# PCU_R3.net
KiCad netlist of a schematic drawn in EAGLE
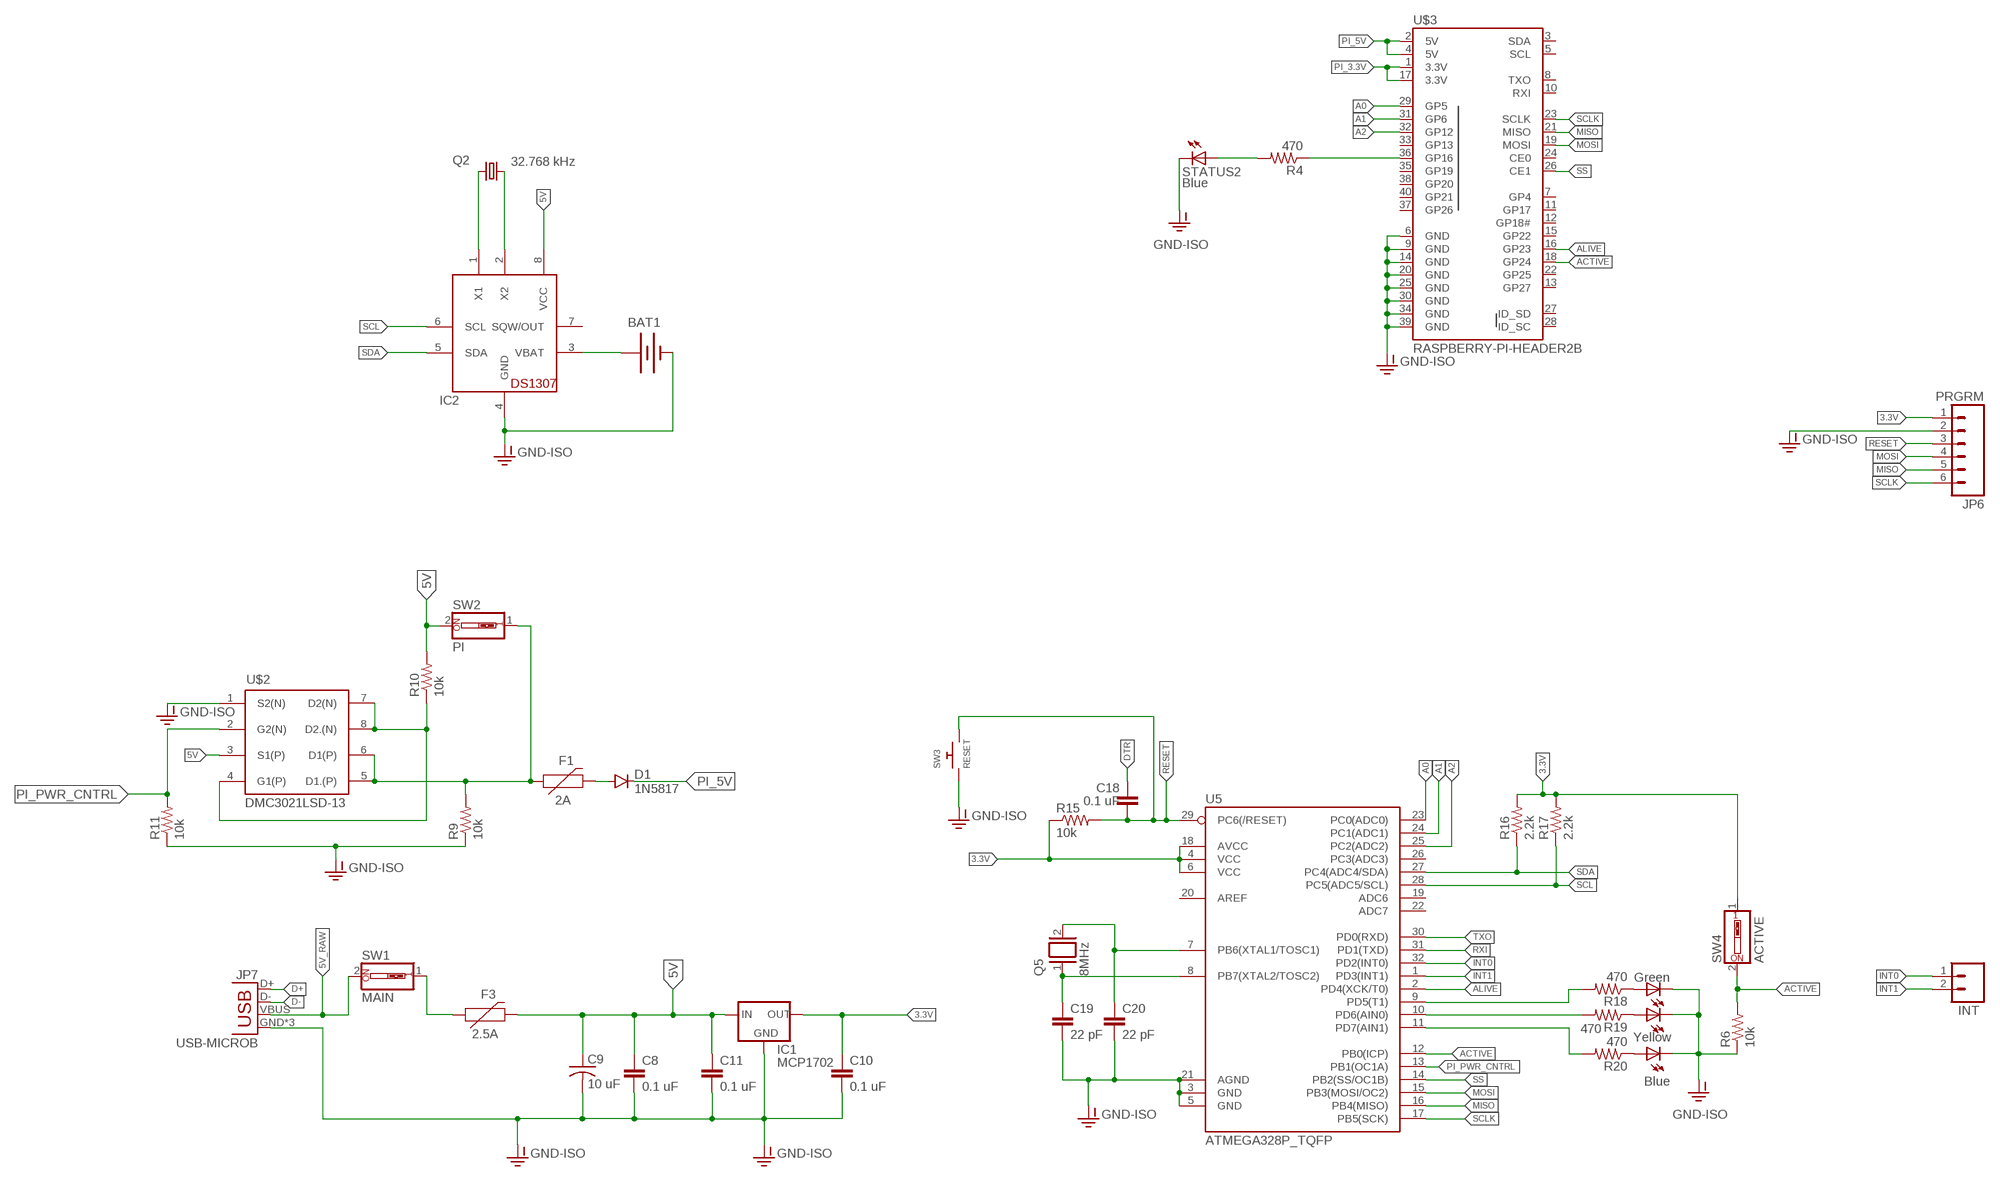
[diagram p0: schematic, sheet 1]

(export (version "E")
  (design (tool "Eeschema 10.0.6"))
  (components
    (comp (ref "BAT1")
      (value "BATTERY12MM")
      (footprint "eagle-import:BATTCON_12MM")
      (libsource (lib "eagle-import") (part "BATTERY12MM"))
    )
    (comp (ref "C8")
      (value "0.1 uF")
      (footprint "eagle-import:1206")
      (libsource (lib "eagle-import") (part "1.0UF-1206-50V-10%"))
    )
    (comp (ref "C9")
      (value "10 uF")
      (footprint "eagle-import:C1206")
      (libsource (lib "eagle-import") (part "C-USC1206"))
    )
    (comp (ref "C10")
      (value "0.1 uF")
      (footprint "eagle-import:1206")
      (libsource (lib "eagle-import") (part "1.0UF-1206-50V-10%"))
    )
    (comp (ref "C11")
      (value "0.1 uF")
      (footprint "eagle-import:1206")
      (libsource (lib "eagle-import") (part "1.0UF-1206-50V-10%"))
    )
    (comp (ref "C18")
      (value "0.1 uF")
      (footprint "eagle-import:1206")
      (libsource (lib "eagle-import") (part "1.0UF-1206-50V-10%"))
    )
    (comp (ref "C19")
      (value "22 pF")
      (footprint "eagle-import:1206")
      (libsource (lib "eagle-import") (part "1.0UF-1206-50V-10%"))
    )
    (comp (ref "C20")
      (value "22 pF")
      (footprint "eagle-import:1206")
      (libsource (lib "eagle-import") (part "1.0UF-1206-50V-10%"))
    )
    (comp (ref "D1")
      (value "1N5817")
      (footprint "eagle-import:DIODE-1N4001")
      (libsource (lib "eagle-import") (part "DIODEPTH"))
    )
    (comp (ref "F1")
      (value "2A")
      (footprint "eagle-import:1206")
      (libsource (lib "eagle-import") (part "PPTC_HALF-AMP"))
    )
    (comp (ref "F3")
      (value "2.5A")
      (footprint "eagle-import:1206")
      (libsource (lib "eagle-import") (part "PPTC_HALF-AMP"))
    )
    (comp (ref "IC1")
      (value "MCP1702")
      (footprint "eagle-import:TO92")
      (libsource (lib "eagle-import") (part "MCP1700TRI"))
    )
    (comp (ref "IC2")
      (value "DS1307")
      (footprint "eagle-import:DIL08")
      (libsource (lib "eagle-import") (part "DS1307"))
    )
    (comp (ref "INT")
      (value "M02PTH")
      (footprint "eagle-import:1X02")
      (libsource (lib "eagle-import") (part "M02PTH"))
    )
    (comp (ref "JP6")
      (value "PRGRM")
      (footprint "eagle-import:1X06")
      (libsource (lib "eagle-import") (part "M06SILK_FEMALE_PTH"))
    )
    (comp (ref "JP7")
      (value "USB-MICROB")
      (footprint "eagle-import:USB-MICROB")
      (libsource (lib "eagle-import") (part "USB-MICROB"))
    )
    (comp (ref "LED6")
      (value "Green")
      (footprint "eagle-import:CHIPLED_1206")
      (libsource (lib "eagle-import") (part "LEDCHIPLED_1206"))
    )
    (comp (ref "LED7")
      (value "Yellow")
      (footprint "eagle-import:CHIPLED_1206")
      (libsource (lib "eagle-import") (part "LEDCHIPLED_1206"))
    )
    (comp (ref "LED8")
      (value "Blue")
      (footprint "eagle-import:CHIPLED_1206")
      (libsource (lib "eagle-import") (part "LEDCHIPLED_1206"))
    )
    (comp (ref "Q2")
      (value "32.768 kHz")
      (footprint "eagle-import:TC38H")
      (libsource (lib "eagle-import") (part "CRYSTALTC38H"))
    )
    (comp (ref "Q5")
      (value "8MHz")
      (footprint "eagle-import:QS")
      (libsource (lib "eagle-import") (part "XTAL/S"))
    )
    (comp (ref "R4")
      (value "470")
      (footprint "eagle-import:1206")
      (libsource (lib "eagle-import") (part "RESISTOR1206"))
    )
    (comp (ref "R6")
      (value "10k")
      (footprint "eagle-import:1206")
      (libsource (lib "eagle-import") (part "RESISTOR1206"))
    )
    (comp (ref "R9")
      (value "10k")
      (footprint "eagle-import:R1206")
      (libsource (lib "eagle-import") (part "R-US_R1206"))
    )
    (comp (ref "R10")
      (value "10k")
      (footprint "eagle-import:R1206")
      (libsource (lib "eagle-import") (part "R-US_R1206"))
    )
    (comp (ref "R11")
      (value "10k")
      (footprint "eagle-import:R1206")
      (libsource (lib "eagle-import") (part "R-US_R1206"))
    )
    (comp (ref "R15")
      (value "10k")
      (footprint "eagle-import:1206")
      (libsource (lib "eagle-import") (part "RESISTOR1206"))
    )
    (comp (ref "R16")
      (value "2.2k")
      (footprint "eagle-import:1206")
      (libsource (lib "eagle-import") (part "RESISTOR1206"))
    )
    (comp (ref "R17")
      (value "2.2k")
      (footprint "eagle-import:1206")
      (libsource (lib "eagle-import") (part "RESISTOR1206"))
    )
    (comp (ref "R18")
      (value "470")
      (footprint "eagle-import:1206")
      (libsource (lib "eagle-import") (part "RESISTOR1206"))
    )
    (comp (ref "R19")
      (value "470")
      (footprint "eagle-import:1206")
      (libsource (lib "eagle-import") (part "RESISTOR1206"))
    )
    (comp (ref "R20")
      (value "470")
      (footprint "eagle-import:1206")
      (libsource (lib "eagle-import") (part "RESISTOR1206"))
    )
    (comp (ref "STATUS2")
      (value "Blue")
      (footprint "eagle-import:CHIPLED_1206")
      (libsource (lib "eagle-import") (part "LEDCHIPLED_1206"))
    )
    (comp (ref "SW1")
      (value "MAIN")
      (footprint "eagle-import:EDG-01")
      (libsource (lib "eagle-import") (part "SW_DIP-1"))
    )
    (comp (ref "SW2")
      (value "PI")
      (footprint "eagle-import:EDG-01")
      (libsource (lib "eagle-import") (part "SW_DIP-1"))
    )
    (comp (ref "SW3")
      (value "RESET")
      (footprint "eagle-import:PUSHBUTTON_SMD_SJ")
      (libsource (lib "eagle-import") (part "SWITCH_PUSHBUTTONSOFTTOUCHSMD_SJ"))
    )
    (comp (ref "SW4")
      (value "ACTIVE")
      (footprint "eagle-import:EDG-01")
      (libsource (lib "eagle-import") (part "SW_DIP-1"))
    )
    (comp (ref "U$2")
      (value "DMC3021LSD-13")
      (footprint "eagle-import:SOIC-8")
      (libsource (lib "eagle-import") (part "DMC3021LSD-13"))
    )
    (comp (ref "U$3")
      (value "RASPBERRY-PI-HEADER2B")
      (footprint "eagle-import:2X20-NOSILK")
      (libsource (lib "eagle-import") (part "RASPBERRY-PI-HEADER2B"))
    )
    (comp (ref "U5")
      (value "ATMEGA328P_TQFP")
      (footprint "eagle-import:TQFP32-08")
      (libsource (lib "eagle-import") (part "ATMEGA328P_TQFP"))
    )
  )
  (nets
    (net (code "1") (name "3.3V") (class "Default")
      (node (ref "C10") (pin "1") (pinfunction "1_1") (pintype "passive"))
      (node (ref "IC1") (pin "3") (pinfunction "OUT_3") (pintype "passive"))
      (node (ref "JP6") (pin "1") (pinfunction "1_1") (pintype "passive"))
      (node (ref "R15") (pin "1") (pinfunction "1_1") (pintype "passive"))
      (node (ref "R16") (pin "2") (pinfunction "2_2") (pintype "passive"))
      (node (ref "R17") (pin "2") (pinfunction "2_2") (pintype "passive"))
      (node (ref "SW4") (pin "1") (pinfunction "1_1") (pintype "passive"))
      (node (ref "U5") (pin "18") (pinfunction "AVCC_18") (pintype "bidirectional"))
      (node (ref "U5") (pin "4") (pinfunction "VCC_4") (pintype "bidirectional"))
      (node (ref "U5") (pin "6") (pinfunction "VCC_6") (pintype "bidirectional"))
    )
    (net (code "2") (name "5V") (class "Default")
      (node (ref "C11") (pin "1") (pinfunction "1_1") (pintype "passive"))
      (node (ref "C8") (pin "1") (pinfunction "1_1") (pintype "passive"))
      (node (ref "C9") (pin "1") (pinfunction "1_1") (pintype "passive"))
      (node (ref "F3") (pin "2") (pinfunction "2_2") (pintype "bidirectional"))
      (node (ref "IC1") (pin "2") (pinfunction "IN_2") (pintype "input"))
      (node (ref "IC2") (pin "8") (pinfunction "VCC_8") (pintype "power_in"))
      (node (ref "R10") (pin "2") (pinfunction "2_2") (pintype "passive"))
      (node (ref "SW2") (pin "2") (pinfunction "2_2") (pintype "passive"))
      (node (ref "U$2") (pin "3") (pinfunction "S1(P)_3") (pintype "bidirectional"))
    )
    (net (code "3") (name "5V_RAW") (class "Default")
      (node (ref "JP7") (pin "VBUS") (pinfunction "VBUS_VBUS") (pintype "bidirectional"))
      (node (ref "SW1") (pin "2") (pinfunction "2_2") (pintype "passive"))
    )
    (net (code "4") (name "A0") (class "Default")
      (node (ref "U$3") (pin "29") (pinfunction "GP5_29") (pintype "bidirectional"))
      (node (ref "U5") (pin "23") (pinfunction "PC0(ADC0)_23") (pintype "bidirectional"))
    )
    (net (code "5") (name "A1") (class "Default")
      (node (ref "U$3") (pin "31") (pinfunction "GP6_31") (pintype "bidirectional"))
      (node (ref "U5") (pin "24") (pinfunction "PC1(ADC1)_24") (pintype "bidirectional"))
    )
    (net (code "6") (name "A2") (class "Default")
      (node (ref "U$3") (pin "32") (pinfunction "GP12_32") (pintype "bidirectional"))
      (node (ref "U5") (pin "25") (pinfunction "PC2(ADC2)_25") (pintype "bidirectional"))
    )
    (net (code "7") (name "ACTIVE") (class "Default")
      (node (ref "R6") (pin "2") (pinfunction "2_2") (pintype "passive"))
      (node (ref "SW4") (pin "2") (pinfunction "2_2") (pintype "passive"))
      (node (ref "U$3") (pin "18") (pinfunction "GP24_18") (pintype "bidirectional"))
      (node (ref "U5") (pin "12") (pinfunction "PB0(ICP)_12") (pintype "bidirectional"))
    )
    (net (code "8") (name "ALIVE") (class "Default")
      (node (ref "U$3") (pin "16") (pinfunction "GP23_16") (pintype "bidirectional"))
      (node (ref "U5") (pin "2") (pinfunction "PD4(XCK/T0)_2") (pintype "bidirectional"))
    )
    (net (code "9") (name "D+") (class "Default")
      (node (ref "JP7") (pin "D+") (pinfunction "D+_D+") (pintype "bidirectional"))
    )
    (net (code "10") (name "D-") (class "Default")
      (node (ref "JP7") (pin "D-") (pinfunction "D-_D-") (pintype "bidirectional"))
    )
    (net (code "11") (name "DTR") (class "Default")
      (node (ref "C18") (pin "1") (pinfunction "1_1") (pintype "passive"))
    )
    (net (code "12") (name "GND-ISO") (class "Default")
      (node (ref "BAT1") (pin "GND") (pinfunction "-_GND") (pintype "power_in"))
      (node (ref "C10") (pin "2") (pinfunction "2_2") (pintype "passive"))
      (node (ref "C11") (pin "2") (pinfunction "2_2") (pintype "passive"))
      (node (ref "C19") (pin "2") (pinfunction "2_2") (pintype "passive"))
      (node (ref "C20") (pin "2") (pinfunction "2_2") (pintype "passive"))
      (node (ref "C8") (pin "2") (pinfunction "2_2") (pintype "passive"))
      (node (ref "C9") (pin "2") (pinfunction "2_2") (pintype "passive"))
      (node (ref "IC1") (pin "1") (pinfunction "GND_1") (pintype "input"))
      (node (ref "IC2") (pin "4") (pinfunction "GND_4") (pintype "power_in"))
      (node (ref "JP6") (pin "2") (pinfunction "2_2") (pintype "passive"))
      (node (ref "JP7") (pin "GND") (pinfunction "GND_GND") (pintype "bidirectional"))
      (node (ref "JP7") (pin "MT1") (pinfunction "GND_MT1") (pintype "bidirectional"))
      (node (ref "JP7") (pin "MT2") (pinfunction "GND_MT2") (pintype "bidirectional"))
      (node (ref "LED6") (pin "C") (pinfunction "C_C") (pintype "passive"))
      (node (ref "LED7") (pin "C") (pinfunction "C_C") (pintype "passive"))
      (node (ref "LED8") (pin "C") (pinfunction "C_C") (pintype "passive"))
      (node (ref "R11") (pin "1") (pinfunction "1_1") (pintype "passive"))
      (node (ref "R6") (pin "1") (pinfunction "1_1") (pintype "passive"))
      (node (ref "R9") (pin "1") (pinfunction "1_1") (pintype "passive"))
      (node (ref "STATUS2") (pin "C") (pinfunction "C_C") (pintype "passive"))
      (node (ref "SW3") (pin "P$1") (pinfunction "P$1_P$1") (pintype "passive"))
      (node (ref "U$2") (pin "1") (pinfunction "S2(N)_1") (pintype "bidirectional"))
      (node (ref "U$3") (pin "14") (pinfunction "GND_14") (pintype "power_in"))
      (node (ref "U$3") (pin "20") (pinfunction "GND_20") (pintype "power_in"))
      (node (ref "U$3") (pin "25") (pinfunction "GND_25") (pintype "power_in"))
      (node (ref "U$3") (pin "30") (pinfunction "GND_30") (pintype "power_in"))
      (node (ref "U$3") (pin "34") (pinfunction "GND_34") (pintype "power_in"))
      (node (ref "U$3") (pin "39") (pinfunction "GND_39") (pintype "power_in"))
      (node (ref "U$3") (pin "6") (pinfunction "GND_6") (pintype "power_in"))
      (node (ref "U$3") (pin "9") (pinfunction "GND_9") (pintype "power_in"))
      (node (ref "U5") (pin "21") (pinfunction "AGND_21") (pintype "bidirectional"))
      (node (ref "U5") (pin "3") (pinfunction "GND_3") (pintype "bidirectional"))
      (node (ref "U5") (pin "5") (pinfunction "GND_5") (pintype "bidirectional"))
    )
    (net (code "13") (name "INT0") (class "Default")
      (node (ref "INT") (pin "1") (pinfunction "1_1") (pintype "passive"))
      (node (ref "U5") (pin "32") (pinfunction "PD2(INT0)_32") (pintype "bidirectional"))
    )
    (net (code "14") (name "INT1") (class "Default")
      (node (ref "INT") (pin "2") (pinfunction "2_2") (pintype "passive"))
      (node (ref "U5") (pin "1") (pinfunction "PD3(INT1)_1") (pintype "bidirectional"))
    )
    (net (code "15") (name "MISO") (class "Default")
      (node (ref "JP6") (pin "5") (pinfunction "5_5") (pintype "passive"))
      (node (ref "U$3") (pin "21") (pinfunction "MISO_21") (pintype "input"))
      (node (ref "U5") (pin "16") (pinfunction "PB4(MISO)_16") (pintype "bidirectional"))
    )
    (net (code "16") (name "MOSI") (class "Default")
      (node (ref "JP6") (pin "4") (pinfunction "4_4") (pintype "passive"))
      (node (ref "U$3") (pin "19") (pinfunction "MOSI_19") (pintype "output"))
      (node (ref "U5") (pin "15") (pinfunction "PB3(MOSI/OC2)_15") (pintype "bidirectional"))
    )
    (net (code "17") (name "Net-(BAT1-+)") (class "Default")
      (node (ref "BAT1") (pin "PWR@1") (pinfunction "+_PWR@1") (pintype "power_in"))
      (node (ref "IC2") (pin "3") (pinfunction "VBAT_3") (pintype "power_in"))
    )
    (net (code "18") (name "Net-(D1-PadA)") (class "Default")
      (node (ref "D1") (pin "A") (pinfunction "A_A") (pintype "passive"))
      (node (ref "F1") (pin "2") (pinfunction "2_2") (pintype "bidirectional"))
    )
    (net (code "19") (name "Net-(F3-Pad1)") (class "Default")
      (node (ref "F3") (pin "1") (pinfunction "1_1") (pintype "bidirectional"))
      (node (ref "SW1") (pin "1") (pinfunction "1_1") (pintype "passive"))
    )
    (net (code "20") (name "Net-(IC2-X1)") (class "Default")
      (node (ref "IC2") (pin "1") (pinfunction "X1_1") (pintype "passive"))
      (node (ref "Q2") (pin "1") (pinfunction "1_1") (pintype "passive"))
    )
    (net (code "21") (name "Net-(IC2-X2)") (class "Default")
      (node (ref "IC2") (pin "2") (pinfunction "X2_2") (pintype "passive"))
      (node (ref "Q2") (pin "2") (pinfunction "2_2") (pintype "passive"))
    )
    (net (code "22") (name "Net-(LED6-PadA)") (class "Default")
      (node (ref "LED6") (pin "A") (pinfunction "A_A") (pintype "passive"))
      (node (ref "R18") (pin "1") (pinfunction "1_1") (pintype "passive"))
    )
    (net (code "23") (name "Net-(LED7-PadA)") (class "Default")
      (node (ref "LED7") (pin "A") (pinfunction "A_A") (pintype "passive"))
      (node (ref "R19") (pin "1") (pinfunction "1_1") (pintype "passive"))
    )
    (net (code "24") (name "Net-(LED8-PadA)") (class "Default")
      (node (ref "LED8") (pin "A") (pinfunction "A_A") (pintype "passive"))
      (node (ref "R20") (pin "1") (pinfunction "1_1") (pintype "passive"))
    )
    (net (code "25") (name "Net-(R4-Pad2)") (class "Default")
      (node (ref "R4") (pin "2") (pinfunction "2_2") (pintype "passive"))
      (node (ref "STATUS2") (pin "A") (pinfunction "A_A") (pintype "passive"))
    )
    (net (code "26") (name "Net-(U$2-D1(P))") (class "Default")
      (node (ref "F1") (pin "1") (pinfunction "1_1") (pintype "bidirectional"))
      (node (ref "R9") (pin "2") (pinfunction "2_2") (pintype "passive"))
      (node (ref "SW2") (pin "1") (pinfunction "1_1") (pintype "passive"))
      (node (ref "U$2") (pin "5") (pinfunction "D1.(P)_5") (pintype "bidirectional"))
      (node (ref "U$2") (pin "6") (pinfunction "D1(P)_6") (pintype "bidirectional"))
    )
    (net (code "27") (name "Net-(U$2-D2(N))") (class "Default")
      (node (ref "R10") (pin "1") (pinfunction "1_1") (pintype "passive"))
      (node (ref "U$2") (pin "4") (pinfunction "G1(P)_4") (pintype "bidirectional"))
      (node (ref "U$2") (pin "7") (pinfunction "D2(N)_7") (pintype "bidirectional"))
      (node (ref "U$2") (pin "8") (pinfunction "D2.(N)_8") (pintype "bidirectional"))
    )
    (net (code "28") (name "Net-(U$3-GP16)") (class "Default")
      (node (ref "R4") (pin "1") (pinfunction "1_1") (pintype "passive"))
      (node (ref "U$3") (pin "36") (pinfunction "GP16_36") (pintype "bidirectional"))
    )
    (net (code "29") (name "Net-(U5-PB6(XTAL1{slash}TOSC1))") (class "Default")
      (node (ref "C20") (pin "1") (pinfunction "1_1") (pintype "passive"))
      (node (ref "Q5") (pin "2") (pinfunction "2_2") (pintype "passive"))
      (node (ref "U5") (pin "7") (pinfunction "PB6(XTAL1/TOSC1)_7") (pintype "bidirectional"))
    )
    (net (code "30") (name "Net-(U5-PB7(XTAL2{slash}TOSC2))") (class "Default")
      (node (ref "C19") (pin "1") (pinfunction "1_1") (pintype "passive"))
      (node (ref "Q5") (pin "1") (pinfunction "1_1") (pintype "passive"))
      (node (ref "U5") (pin "8") (pinfunction "PB7(XTAL2/TOSC2)_8") (pintype "bidirectional"))
    )
    (net (code "31") (name "Net-(U5-PD5(T1))") (class "Default")
      (node (ref "R18") (pin "2") (pinfunction "2_2") (pintype "passive"))
      (node (ref "U5") (pin "9") (pinfunction "PD5(T1)_9") (pintype "bidirectional"))
    )
    (net (code "32") (name "Net-(U5-PD6(AIN0))") (class "Default")
      (node (ref "R19") (pin "2") (pinfunction "2_2") (pintype "passive"))
      (node (ref "U5") (pin "10") (pinfunction "PD6(AIN0)_10") (pintype "bidirectional"))
    )
    (net (code "33") (name "Net-(U5-PD7(AIN1))") (class "Default")
      (node (ref "R20") (pin "2") (pinfunction "2_2") (pintype "passive"))
      (node (ref "U5") (pin "11") (pinfunction "PD7(AIN1)_11") (pintype "bidirectional"))
    )
    (net (code "34") (name "PI_3.3V") (class "Default")
      (node (ref "U$3") (pin "1") (pinfunction "3.3V_1") (pintype "power_in"))
      (node (ref "U$3") (pin "17") (pinfunction "3.3V_17") (pintype "power_in"))
    )
    (net (code "35") (name "PI_5V") (class "Default")
      (node (ref "D1") (pin "C") (pinfunction "C_C") (pintype "passive"))
      (node (ref "U$3") (pin "2") (pinfunction "5V_2") (pintype "power_in"))
      (node (ref "U$3") (pin "4") (pinfunction "5V_4") (pintype "power_in"))
    )
    (net (code "36") (name "PI_PWR_CNTRL") (class "Default")
      (node (ref "R11") (pin "2") (pinfunction "2_2") (pintype "passive"))
      (node (ref "U$2") (pin "2") (pinfunction "G2(N)_2") (pintype "bidirectional"))
      (node (ref "U5") (pin "13") (pinfunction "PB1(OC1A)_13") (pintype "bidirectional"))
    )
    (net (code "37") (name "RESET") (class "Default")
      (node (ref "C18") (pin "2") (pinfunction "2_2") (pintype "passive"))
      (node (ref "JP6") (pin "3") (pinfunction "3_3") (pintype "passive"))
      (node (ref "R15") (pin "2") (pinfunction "2_2") (pintype "passive"))
      (node (ref "SW3") (pin "P$2") (pinfunction "P$2_P$2") (pintype "passive"))
      (node (ref "U5") (pin "29") (pinfunction "PC6(/RESET)_29") (pintype "bidirectional"))
    )
    (net (code "38") (name "RXI") (class "Default")
      (node (ref "U5") (pin "31") (pinfunction "PD1(TXD)_31") (pintype "bidirectional"))
    )
    (net (code "39") (name "SCL") (class "Default")
      (node (ref "IC2") (pin "6") (pinfunction "SCL_6") (pintype "bidirectional"))
      (node (ref "R17") (pin "1") (pinfunction "1_1") (pintype "passive"))
      (node (ref "U5") (pin "28") (pinfunction "PC5(ADC5/SCL)_28") (pintype "bidirectional"))
    )
    (net (code "40") (name "SCLK") (class "Default")
      (node (ref "JP6") (pin "6") (pinfunction "6_6") (pintype "passive"))
      (node (ref "U$3") (pin "23") (pinfunction "SCLK_23") (pintype "output"))
      (node (ref "U5") (pin "17") (pinfunction "PB5(SCK)_17") (pintype "bidirectional"))
    )
    (net (code "41") (name "SDA") (class "Default")
      (node (ref "IC2") (pin "5") (pinfunction "SDA_5") (pintype "bidirectional"))
      (node (ref "R16") (pin "1") (pinfunction "1_1") (pintype "passive"))
      (node (ref "U5") (pin "27") (pinfunction "PC4(ADC4/SDA)_27") (pintype "bidirectional"))
    )
    (net (code "42") (name "SS") (class "Default")
      (node (ref "U$3") (pin "26") (pinfunction "CE1_26") (pintype "output"))
      (node (ref "U5") (pin "14") (pinfunction "PB2(SS/OC1B)_14") (pintype "bidirectional"))
    )
    (net (code "43") (name "TXO") (class "Default")
      (node (ref "U5") (pin "30") (pinfunction "PD0(RXD)_30") (pintype "bidirectional"))
    )
    (net (code "44") (name "unconnected-(IC2-SQW{slash}OUT-Pad7)") (class "Default")
      (node (ref "IC2") (pin "7") (pinfunction "SQW/OUT_7") (pintype "bidirectional"))
    )
    (net (code "45") (name "unconnected-(U$3-CE0-Pad24)") (class "Default")
      (node (ref "U$3") (pin "24") (pinfunction "CE0_24") (pintype "output"))
    )
    (net (code "46") (name "unconnected-(U$3-GP4-Pad7)") (class "Default")
      (node (ref "U$3") (pin "7") (pinfunction "GP4_7") (pintype "bidirectional"))
    )
    (net (code "47") (name "unconnected-(U$3-GP13-Pad33)") (class "Default")
      (node (ref "U$3") (pin "33") (pinfunction "GP13_33") (pintype "bidirectional"))
    )
    (net (code "48") (name "unconnected-(U$3-GP17-Pad11)") (class "Default")
      (node (ref "U$3") (pin "11") (pinfunction "GP17_11") (pintype "bidirectional"))
    )
    (net (code "49") (name "unconnected-(U$3-GP18#-Pad12)") (class "Default")
      (node (ref "U$3") (pin "12") (pinfunction "GP18#_12") (pintype "bidirectional"))
    )
    (net (code "50") (name "unconnected-(U$3-GP19-Pad35)") (class "Default")
      (node (ref "U$3") (pin "35") (pinfunction "GP19_35") (pintype "bidirectional"))
    )
    (net (code "51") (name "unconnected-(U$3-GP20-Pad38)") (class "Default")
      (node (ref "U$3") (pin "38") (pinfunction "GP20_38") (pintype "bidirectional"))
    )
    (net (code "52") (name "unconnected-(U$3-GP21-Pad40)") (class "Default")
      (node (ref "U$3") (pin "40") (pinfunction "GP21_40") (pintype "bidirectional"))
    )
    (net (code "53") (name "unconnected-(U$3-GP22-Pad15)") (class "Default")
      (node (ref "U$3") (pin "15") (pinfunction "GP22_15") (pintype "bidirectional"))
    )
    (net (code "54") (name "unconnected-(U$3-GP25-Pad22)") (class "Default")
      (node (ref "U$3") (pin "22") (pinfunction "GP25_22") (pintype "bidirectional"))
    )
    (net (code "55") (name "unconnected-(U$3-GP26-Pad37)") (class "Default")
      (node (ref "U$3") (pin "37") (pinfunction "GP26_37") (pintype "bidirectional"))
    )
    (net (code "56") (name "unconnected-(U$3-GP27-Pad13)") (class "Default")
      (node (ref "U$3") (pin "13") (pinfunction "GP27_13") (pintype "bidirectional"))
    )
    (net (code "57") (name "unconnected-(U$3-ID_SC-Pad28)") (class "Default")
      (node (ref "U$3") (pin "28") (pinfunction "ID_SC_28") (pintype "bidirectional"))
    )
    (net (code "58") (name "unconnected-(U$3-ID_SD-Pad27)") (class "Default")
      (node (ref "U$3") (pin "27") (pinfunction "ID_SD_27") (pintype "bidirectional"))
    )
    (net (code "59") (name "unconnected-(U$3-RXI-Pad10)") (class "Default")
      (node (ref "U$3") (pin "10") (pinfunction "RXI_10") (pintype "input"))
    )
    (net (code "60") (name "unconnected-(U$3-SCL-Pad5)") (class "Default")
      (node (ref "U$3") (pin "5") (pinfunction "SCL_5") (pintype "bidirectional"))
    )
    (net (code "61") (name "unconnected-(U$3-SDA-Pad3)") (class "Default")
      (node (ref "U$3") (pin "3") (pinfunction "SDA_3") (pintype "bidirectional"))
    )
    (net (code "62") (name "unconnected-(U$3-TXO-Pad8)") (class "Default")
      (node (ref "U$3") (pin "8") (pinfunction "TXO_8") (pintype "output"))
    )
    (net (code "63") (name "unconnected-(U5-ADC6-Pad19)") (class "Default")
      (node (ref "U5") (pin "19") (pinfunction "ADC6_19") (pintype "bidirectional"))
    )
    (net (code "64") (name "unconnected-(U5-ADC7-Pad22)") (class "Default")
      (node (ref "U5") (pin "22") (pinfunction "ADC7_22") (pintype "bidirectional"))
    )
    (net (code "65") (name "unconnected-(U5-AREF-Pad20)") (class "Default")
      (node (ref "U5") (pin "20") (pinfunction "AREF_20") (pintype "bidirectional"))
    )
    (net (code "66") (name "unconnected-(U5-PC3(ADC3)-Pad26)") (class "Default")
      (node (ref "U5") (pin "26") (pinfunction "PC3(ADC3)_26") (pintype "bidirectional"))
    )
  )
)
